# USB_OTG.net
KiCad netlist of a schematic drawn in Altium Designer
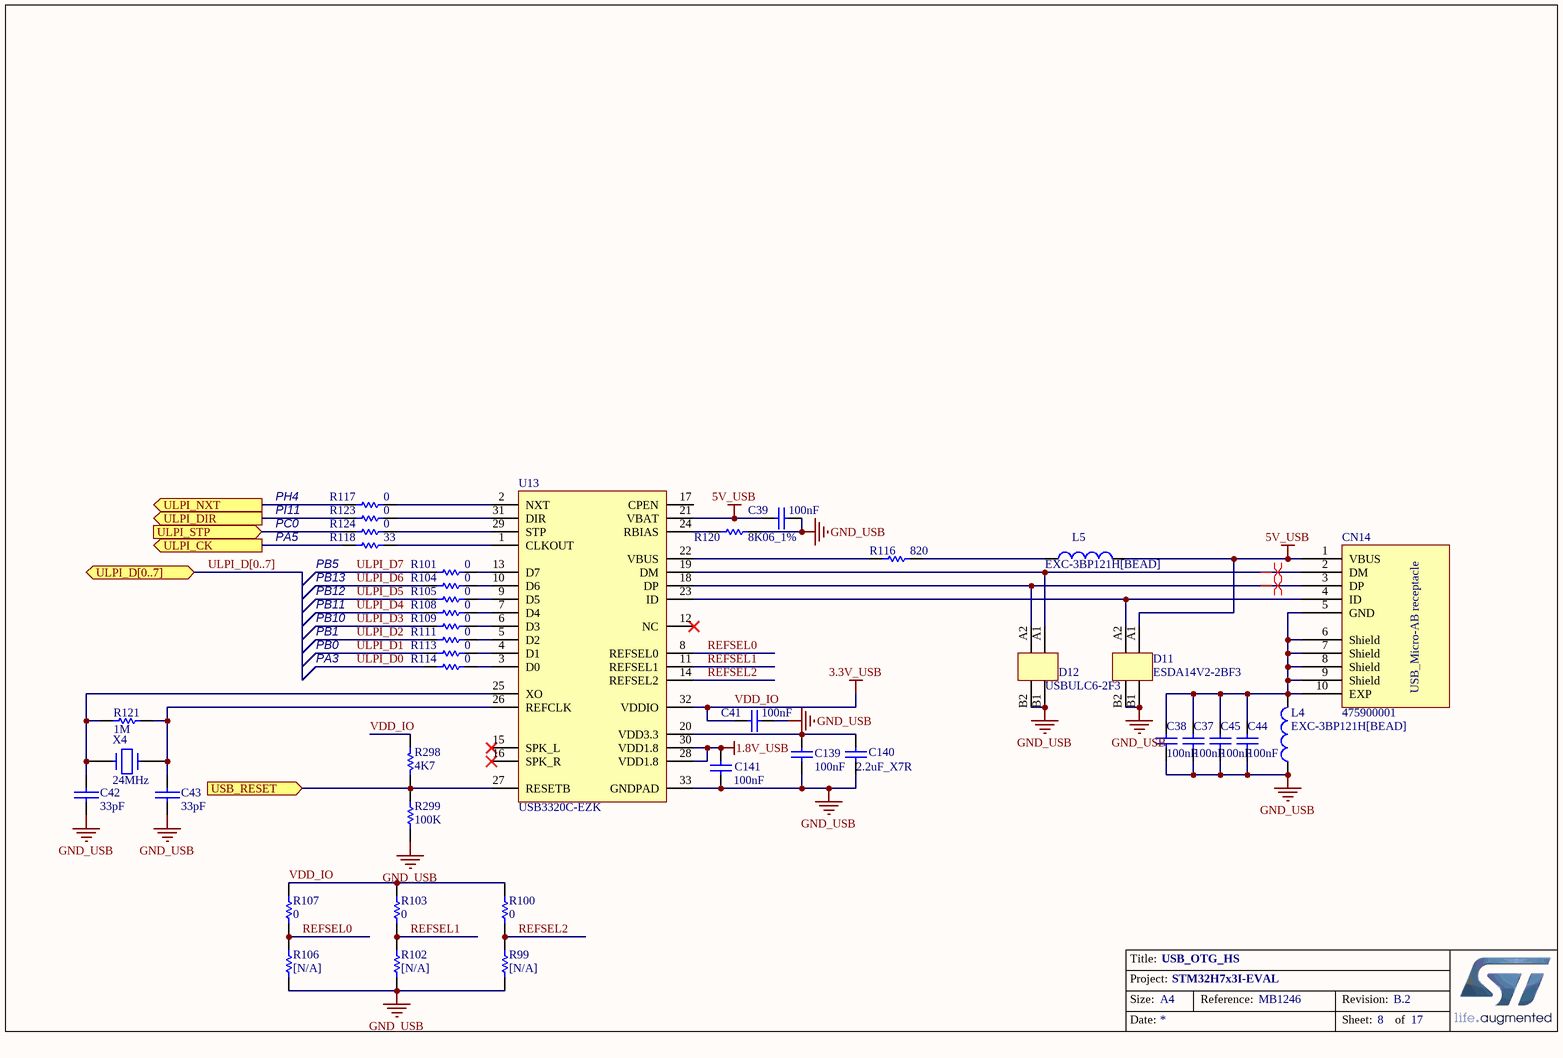
[diagram p0: USB_OTG.SchDoc]

(export (version "E")
  (design (tool "Eeschema 10.0.6"))
  (components
    (comp (ref "C37")
      (value "100nF")
      (footprint "0603C")
      (description "Capacitor")
      (fields (field (name "PUBLISHER") "Altium Limited"))
      (libsource (lib "Miscellaneous Devices") (part "Cap"))
    )
    (comp (ref "C38")
      (value "100nF")
      (footprint "0603C")
      (description "Capacitor")
      (fields (field (name "PUBLISHER") "Altium Limited"))
      (libsource (lib "Miscellaneous Devices") (part "Cap"))
    )
    (comp (ref "C39")
      (value "100nF")
      (footprint "0603C")
      (description "Capacitor")
      (fields (field (name "PUBLISHER") "Altium Limited"))
      (libsource (lib "Miscellaneous Devices") (part "Cap"))
    )
    (comp (ref "C41")
      (value "100nF")
      (footprint "0603C")
      (description "Capacitor")
      (fields (field (name "PUBLISHER") "Altium Limited"))
      (libsource (lib "Miscellaneous Devices") (part "Cap"))
    )
    (comp (ref "C42")
      (value "33pF")
      (footprint "0603C")
      (description "Capacitor")
      (libsource (lib "*") (part "CAP"))
    )
    (comp (ref "C43")
      (value "33pF")
      (footprint "0603C")
      (description "Capacitor")
      (libsource (lib "*") (part "CAP"))
    )
    (comp (ref "C44")
      (value "100nF")
      (footprint "0603C")
      (description "Capacitor")
      (fields (field (name "PUBLISHER") "Altium Limited"))
      (libsource (lib "Miscellaneous Devices") (part "Cap"))
    )
    (comp (ref "C45")
      (value "100nF")
      (footprint "0603C")
      (description "Capacitor")
      (fields (field (name "PUBLISHER") "Altium Limited"))
      (libsource (lib "Miscellaneous Devices") (part "Cap"))
    )
    (comp (ref "C139")
      (value "100nF")
      (footprint "0603C")
      (description "Capacitor")
      (fields (field (name "PUBLISHER") "Altium Limited"))
      (libsource (lib "Miscellaneous Devices") (part "Cap"))
    )
    (comp (ref "C140")
      (value "2.2uF_X7R")
      (footprint "0603C")
      (description "Capacitor")
      (fields (field (name "PUBLISHER") "Altium Limited"))
      (libsource (lib "Miscellaneous Devices") (part "Cap"))
    )
    (comp (ref "C141")
      (value "100nF")
      (footprint "0603C")
      (description "Capacitor")
      (fields (field (name "PUBLISHER") "Altium Limited"))
      (libsource (lib "Miscellaneous Devices") (part "Cap"))
    )
    (comp (ref "CN14")
      (value "475900001")
      (footprint "MOLEX_47590001")
      (libsource (lib "mb1045") (part "475900001"))
    )
    (comp (ref "D11")
      (value "ESDA14V2-2BF3")
      (footprint "BGA4_0R4_0R8X0R8")
      (libsource (lib "MB786") (part "ESDA14V2-2BF3"))
    )
    (comp (ref "D12")
      (value "USBULC6-2F3")
      (footprint "BGA4_0R4_1X1")
      (libsource (lib "MB786") (part "USBULC6-2F3"))
    )
    (comp (ref "L4")
      (value "EXC-3BP121H[BEAD]")
      (footprint "0603L")
      (description "Inductor")
      (fields (field (name "PUBLISHER") "Altium Limited"))
      (libsource (lib "Miscellaneous Devices") (part "Inductor"))
    )
    (comp (ref "L5")
      (value "EXC-3BP121H[BEAD]")
      (footprint "0603L")
      (description "Inductor")
      (fields (field (name "PUBLISHER") "Altium Limited"))
      (libsource (lib "Miscellaneous Devices") (part "Inductor"))
    )
    (comp (ref "R99")
      (value "[N/A]")
      (footprint "0603R")
      (description "Resistor")
      (fields (field (name "PUBLISHER") "Altium Limited"))
      (libsource (lib "Miscellaneous Devices") (part "Res1"))
    )
    (comp (ref "R100")
      (value "0")
      (footprint "0603R")
      (description "Resistor")
      (fields (field (name "PUBLISHER") "Altium Limited"))
      (libsource (lib "Miscellaneous Devices") (part "Res1"))
    )
    (comp (ref "R101")
      (value "0")
      (footprint "0603R")
      (description "Resistor")
      (fields (field (name "PUBLISHER") "Altium Limited"))
      (libsource (lib "Miscellaneous Devices") (part "Res1"))
    )
    (comp (ref "R102")
      (value "[N/A]")
      (footprint "0603R")
      (description "Resistor")
      (fields (field (name "PUBLISHER") "Altium Limited"))
      (libsource (lib "Miscellaneous Devices") (part "Res1"))
    )
    (comp (ref "R103")
      (value "0")
      (footprint "0603R")
      (description "Resistor")
      (fields (field (name "PUBLISHER") "Altium Limited"))
      (libsource (lib "Miscellaneous Devices") (part "Res1"))
    )
    (comp (ref "R104")
      (value "0")
      (footprint "0603R")
      (description "Resistor")
      (fields (field (name "PUBLISHER") "Altium Limited"))
      (libsource (lib "Miscellaneous Devices") (part "Res1"))
    )
    (comp (ref "R105")
      (value "0")
      (footprint "0603R")
      (description "Resistor")
      (fields (field (name "PUBLISHER") "Altium Limited"))
      (libsource (lib "Miscellaneous Devices") (part "Res1"))
    )
    (comp (ref "R106")
      (value "[N/A]")
      (footprint "0603R")
      (description "Resistor")
      (fields (field (name "PUBLISHER") "Altium Limited"))
      (libsource (lib "Miscellaneous Devices") (part "Res1"))
    )
    (comp (ref "R107")
      (value "0")
      (footprint "0603R")
      (description "Resistor")
      (fields (field (name "PUBLISHER") "Altium Limited"))
      (libsource (lib "Miscellaneous Devices") (part "Res1"))
    )
    (comp (ref "R108")
      (value "0")
      (footprint "0603R")
      (description "Resistor")
      (fields (field (name "PUBLISHER") "Altium Limited"))
      (libsource (lib "Miscellaneous Devices") (part "Res1"))
    )
    (comp (ref "R109")
      (value "0")
      (footprint "0603R")
      (description "Resistor")
      (fields (field (name "PUBLISHER") "Altium Limited"))
      (libsource (lib "Miscellaneous Devices") (part "Res1"))
    )
    (comp (ref "R111")
      (value "0")
      (footprint "0603R")
      (description "Resistor")
      (fields (field (name "PUBLISHER") "Altium Limited"))
      (libsource (lib "Miscellaneous Devices") (part "Res1"))
    )
    (comp (ref "R113")
      (value "0")
      (footprint "0603R")
      (description "Resistor")
      (fields (field (name "PUBLISHER") "Altium Limited"))
      (libsource (lib "Miscellaneous Devices") (part "Res1"))
    )
    (comp (ref "R114")
      (value "0")
      (footprint "0603R")
      (description "Resistor")
      (fields (field (name "PUBLISHER") "Altium Limited"))
      (libsource (lib "Miscellaneous Devices") (part "Res1"))
    )
    (comp (ref "R116")
      (value "820")
      (footprint "0603R")
      (description "Resistor")
      (fields (field (name "PUBLISHER") "Altium Limited"))
      (libsource (lib "Miscellaneous Devices") (part "res1"))
    )
    (comp (ref "R117")
      (value "0")
      (footprint "0603R")
      (description "Resistor")
      (fields (field (name "PUBLISHER") "Altium Limited"))
      (libsource (lib "Miscellaneous Devices") (part "Res1"))
    )
    (comp (ref "R118")
      (value "33")
      (footprint "0603R")
      (description "Resistor")
      (fields (field (name "PUBLISHER") "Altium Limited"))
      (libsource (lib "Miscellaneous Devices") (part "Res1"))
    )
    (comp (ref "R120")
      (value "8K06_1%")
      (footprint "0603R")
      (description "Resistor,8K06,0402,1%,YAGEO")
      (libsource (lib "MCD_TOOLS") (part "Res_8K06_1%_0402"))
    )
    (comp (ref "R121")
      (value "1M")
      (footprint "0603R")
      (description "Resistor")
      (fields (field (name "PUBLISHER") "Altium Limited"))
      (libsource (lib "Miscellaneous Devices") (part "Res1"))
    )
    (comp (ref "R123")
      (value "0")
      (footprint "0603R")
      (description "Resistor")
      (fields (field (name "PUBLISHER") "Altium Limited"))
      (libsource (lib "Miscellaneous Devices") (part "Res1"))
    )
    (comp (ref "R124")
      (value "0")
      (footprint "0603R")
      (description "Resistor")
      (fields (field (name "PUBLISHER") "Altium Limited"))
      (libsource (lib "Miscellaneous Devices") (part "Res1"))
    )
    (comp (ref "R298")
      (value "4K7")
      (footprint "0603R")
      (description "Resistor")
      (fields (field (name "PUBLISHER") "Altium Limited"))
      (libsource (lib "*") (part "Res1"))
    )
    (comp (ref "R299")
      (value "100K")
      (footprint "0603R")
      (description "Resistor 0402 / 0603 / 0805")
      (libsource (lib "") (part "Res1_1"))
    )
    (comp (ref "U13")
      (value "USB3320C-EZK")
      (footprint "QFN32_0R5_5X5")
      (description "USB3320C,  Hi-Speed USB Host, Device or OTG PHY with ULPI Low Pin Interface")
      (libsource (lib "MCD_TOOLS") (part "USB3320C-EZK"))
    )
    (comp (ref "X4")
      (value "24MHz")
      (footprint "XTAL1")
      (description "Crystal")
      (libsource (lib "*") (part "CRYSTAL"))
    )
  )
  (nets
    (net (code "1") (name "/REFSEL0") (class "Default")
      (node (ref "R106") (pin "2") (pinfunction "2_2") (pintype "passive"))
      (node (ref "R107") (pin "1") (pinfunction "1_1") (pintype "passive"))
      (node (ref "U13") (pin "8") (pinfunction "REFSEL0_8") (pintype "passive"))
    )
    (net (code "2") (name "/REFSEL1") (class "Default")
      (node (ref "R102") (pin "2") (pinfunction "2_2") (pintype "passive"))
      (node (ref "R103") (pin "1") (pinfunction "1_1") (pintype "passive"))
      (node (ref "U13") (pin "11") (pinfunction "REFSEL1_11") (pintype "passive"))
    )
    (net (code "3") (name "/REFSEL2") (class "Default")
      (node (ref "R100") (pin "1") (pinfunction "1_1") (pintype "passive"))
      (node (ref "R99") (pin "2") (pinfunction "2_2") (pintype "passive"))
      (node (ref "U13") (pin "14") (pinfunction "REFSEL2_14") (pintype "passive"))
    )
    (net (code "4") (name "/ULPI_CK") (class "Default")
      (node (ref "R118") (pin "2") (pinfunction "2_2") (pintype "passive"))
    )
    (net (code "5") (name "/ULPI_D0") (class "Default")
      (node (ref "R114") (pin "2") (pinfunction "2_2") (pintype "passive"))
    )
    (net (code "6") (name "/ULPI_D1") (class "Default")
      (node (ref "R113") (pin "2") (pinfunction "2_2") (pintype "passive"))
    )
    (net (code "7") (name "/ULPI_D2") (class "Default")
      (node (ref "R111") (pin "2") (pinfunction "2_2") (pintype "passive"))
    )
    (net (code "8") (name "/ULPI_D3") (class "Default")
      (node (ref "R109") (pin "2") (pinfunction "2_2") (pintype "passive"))
    )
    (net (code "9") (name "/ULPI_D4") (class "Default")
      (node (ref "R108") (pin "2") (pinfunction "2_2") (pintype "passive"))
    )
    (net (code "10") (name "/ULPI_D5") (class "Default")
      (node (ref "R105") (pin "2") (pinfunction "2_2") (pintype "passive"))
    )
    (net (code "11") (name "/ULPI_D6") (class "Default")
      (node (ref "R104") (pin "2") (pinfunction "2_2") (pintype "passive"))
    )
    (net (code "12") (name "/ULPI_D7") (class "Default")
      (node (ref "R101") (pin "2") (pinfunction "2_2") (pintype "passive"))
    )
    (net (code "13") (name "/ULPI_DIR") (class "Default")
      (node (ref "R123") (pin "2") (pinfunction "2_2") (pintype "passive"))
    )
    (net (code "15") (name "/ULPI_NXT") (class "Default")
      (node (ref "R117") (pin "2") (pinfunction "2_2") (pintype "passive"))
    )
    (net (code "16") (name "/ULPI_STP") (class "Default")
      (node (ref "R124") (pin "2") (pinfunction "2_2") (pintype "passive"))
    )
    (net (code "17") (name "/USB_RESET") (class "Default")
      (node (ref "R298") (pin "1") (pinfunction "1_1") (pintype "passive"))
      (node (ref "R299") (pin "2") (pinfunction "2_2") (pintype "passive"))
      (node (ref "U13") (pin "27") (pinfunction "RESETB_27") (pintype "passive"))
    )
    (net (code "18") (name "1.8V_USB") (class "Default")
      (node (ref "C141") (pin "1") (pinfunction "1_1") (pintype "passive"))
      (node (ref "U13") (pin "28") (pinfunction "VDD1.8_28") (pintype "passive"))
      (node (ref "U13") (pin "30") (pinfunction "VDD1.8_30") (pintype "passive"))
    )
    (net (code "19") (name "3.3V_USB") (class "Default")
      (node (ref "C41") (pin "1") (pinfunction "1_1") (pintype "passive"))
      (node (ref "R100") (pin "2") (pinfunction "2_2") (pintype "passive"))
      (node (ref "R103") (pin "2") (pinfunction "2_2") (pintype "passive"))
      (node (ref "R107") (pin "2") (pinfunction "2_2") (pintype "passive"))
      (node (ref "R298") (pin "2") (pinfunction "2_2") (pintype "passive"))
      (node (ref "U13") (pin "32") (pinfunction "VDDIO_32") (pintype "passive"))
    )
    (net (code "20") (name "5V_USB") (class "Default")
      (node (ref "C39") (pin "1") (pinfunction "1_1") (pintype "passive"))
      (node (ref "CN14") (pin "1") (pinfunction "VBUS_1") (pintype "passive"))
      (node (ref "D11") (pin "A1") (pintype "passive"))
      (node (ref "L5") (pin "2") (pinfunction "2_2") (pintype "passive"))
      (node (ref "U13") (pin "21") (pinfunction "VBAT_21") (pintype "passive"))
    )
    (net (code "21") (name "GND_USB") (class "Default")
      (node (ref "C139") (pin "2") (pinfunction "2_2") (pintype "passive"))
      (node (ref "C140") (pin "1") (pinfunction "1_1") (pintype "passive"))
      (node (ref "C141") (pin "2") (pinfunction "2_2") (pintype "passive"))
      (node (ref "C37") (pin "2") (pinfunction "2_2") (pintype "passive"))
      (node (ref "C38") (pin "2") (pinfunction "2_2") (pintype "passive"))
      (node (ref "C39") (pin "2") (pinfunction "2_2") (pintype "passive"))
      (node (ref "C41") (pin "2") (pinfunction "2_2") (pintype "passive"))
      (node (ref "C42") (pin "2") (pinfunction "2_2") (pintype "passive"))
      (node (ref "C43") (pin "2") (pinfunction "2_2") (pintype "passive"))
      (node (ref "C44") (pin "2") (pinfunction "2_2") (pintype "passive"))
      (node (ref "C45") (pin "2") (pinfunction "2_2") (pintype "passive"))
      (node (ref "D11") (pin "B1") (pintype "passive"))
      (node (ref "D11") (pin "B2") (pintype "passive"))
      (node (ref "D12") (pin "B1") (pintype "passive"))
      (node (ref "D12") (pin "B2") (pintype "passive"))
      (node (ref "L4") (pin "1") (pinfunction "1_1") (pintype "passive"))
      (node (ref "R102") (pin "1") (pinfunction "1_1") (pintype "passive"))
      (node (ref "R106") (pin "1") (pinfunction "1_1") (pintype "passive"))
      (node (ref "R120") (pin "2") (pinfunction "2_2") (pintype "passive"))
      (node (ref "R299") (pin "1") (pinfunction "1_1") (pintype "passive"))
      (node (ref "R99") (pin "1") (pinfunction "1_1") (pintype "passive"))
      (node (ref "U13") (pin "33") (pinfunction "GNDPAD_33") (pintype "passive"))
    )
    (net (code "22") (name "Net-(CN14-DM)") (class "Default")
      (node (ref "CN14") (pin "2") (pinfunction "DM_2") (pintype "passive"))
      (node (ref "D12") (pin "A1") (pintype "passive"))
      (node (ref "U13") (pin "19") (pinfunction "DM_19") (pintype "passive"))
    )
    (net (code "23") (name "Net-(CN14-DP)") (class "Default")
      (node (ref "CN14") (pin "3") (pinfunction "DP_3") (pintype "passive"))
      (node (ref "D12") (pin "A2") (pintype "passive"))
      (node (ref "U13") (pin "18") (pinfunction "DP_18") (pintype "passive"))
    )
    (net (code "24") (name "Net-(CN14-EXP)") (class "Default")
      (node (ref "C37") (pin "1") (pinfunction "1_1") (pintype "passive"))
      (node (ref "C38") (pin "1") (pinfunction "1_1") (pintype "passive"))
      (node (ref "C44") (pin "1") (pinfunction "1_1") (pintype "passive"))
      (node (ref "C45") (pin "1") (pinfunction "1_1") (pintype "passive"))
      (node (ref "CN14") (pin "10") (pinfunction "EXP_10") (pintype "passive"))
      (node (ref "CN14") (pin "5") (pinfunction "GND_5") (pintype "passive"))
      (node (ref "CN14") (pin "6") (pinfunction "Shield_6") (pintype "passive"))
      (node (ref "CN14") (pin "7") (pinfunction "Shield_7") (pintype "passive"))
      (node (ref "CN14") (pin "8") (pinfunction "Shield_8") (pintype "passive"))
      (node (ref "CN14") (pin "9") (pinfunction "Shield_9") (pintype "passive"))
      (node (ref "L4") (pin "2") (pinfunction "2_2") (pintype "passive"))
    )
    (net (code "25") (name "Net-(CN14-ID)") (class "Default")
      (node (ref "CN14") (pin "4") (pinfunction "ID_4") (pintype "passive"))
      (node (ref "D11") (pin "A2") (pintype "passive"))
      (node (ref "U13") (pin "23") (pinfunction "ID_23") (pintype "passive"))
    )
    (net (code "26") (name "Net-(L5-Pad1)") (class "Default")
      (node (ref "L5") (pin "1") (pinfunction "1_1") (pintype "passive"))
      (node (ref "R116") (pin "2") (pinfunction "2_2") (pintype "passive"))
    )
    (net (code "27") (name "Net-(U13-CLKOUT)") (class "Default")
      (node (ref "R118") (pin "1") (pinfunction "1_1") (pintype "passive"))
      (node (ref "U13") (pin "1") (pinfunction "CLKOUT_1") (pintype "passive"))
    )
    (net (code "28") (name "Net-(U13-D0)") (class "Default")
      (node (ref "R114") (pin "1") (pinfunction "1_1") (pintype "passive"))
      (node (ref "U13") (pin "3") (pinfunction "D0_3") (pintype "passive"))
    )
    (net (code "29") (name "Net-(U13-D1)") (class "Default")
      (node (ref "R113") (pin "1") (pinfunction "1_1") (pintype "passive"))
      (node (ref "U13") (pin "4") (pinfunction "D1_4") (pintype "passive"))
    )
    (net (code "30") (name "Net-(U13-D2)") (class "Default")
      (node (ref "R111") (pin "1") (pinfunction "1_1") (pintype "passive"))
      (node (ref "U13") (pin "5") (pinfunction "D2_5") (pintype "passive"))
    )
    (net (code "31") (name "Net-(U13-D3)") (class "Default")
      (node (ref "R109") (pin "1") (pinfunction "1_1") (pintype "passive"))
      (node (ref "U13") (pin "6") (pinfunction "D3_6") (pintype "passive"))
    )
    (net (code "32") (name "Net-(U13-D4)") (class "Default")
      (node (ref "R108") (pin "1") (pinfunction "1_1") (pintype "passive"))
      (node (ref "U13") (pin "7") (pinfunction "D4_7") (pintype "passive"))
    )
    (net (code "33") (name "Net-(U13-D5)") (class "Default")
      (node (ref "R105") (pin "1") (pinfunction "1_1") (pintype "passive"))
      (node (ref "U13") (pin "9") (pinfunction "D5_9") (pintype "passive"))
    )
    (net (code "34") (name "Net-(U13-D6)") (class "Default")
      (node (ref "R104") (pin "1") (pinfunction "1_1") (pintype "passive"))
      (node (ref "U13") (pin "10") (pinfunction "D6_10") (pintype "passive"))
    )
    (net (code "35") (name "Net-(U13-D7)") (class "Default")
      (node (ref "R101") (pin "1") (pinfunction "1_1") (pintype "passive"))
      (node (ref "U13") (pin "13") (pinfunction "D7_13") (pintype "passive"))
    )
    (net (code "36") (name "Net-(U13-DIR)") (class "Default")
      (node (ref "R123") (pin "1") (pinfunction "1_1") (pintype "passive"))
      (node (ref "U13") (pin "31") (pinfunction "DIR_31") (pintype "passive"))
    )
    (net (code "37") (name "Net-(U13-NXT)") (class "Default")
      (node (ref "R117") (pin "1") (pinfunction "1_1") (pintype "passive"))
      (node (ref "U13") (pin "2") (pinfunction "NXT_2") (pintype "passive"))
    )
    (net (code "38") (name "Net-(U13-RBIAS)") (class "Default")
      (node (ref "R120") (pin "1") (pinfunction "1_1") (pintype "passive"))
      (node (ref "U13") (pin "24") (pinfunction "RBIAS_24") (pintype "passive"))
    )
    (net (code "39") (name "Net-(U13-REFCLK)") (class "Default")
      (node (ref "C43") (pin "1") (pinfunction "1_1") (pintype "passive"))
      (node (ref "R121") (pin "2") (pinfunction "2_2") (pintype "passive"))
      (node (ref "U13") (pin "26") (pinfunction "REFCLK_26") (pintype "passive"))
      (node (ref "X4") (pin "1") (pinfunction "1_1") (pintype "passive"))
    )
    (net (code "40") (name "Net-(U13-STP)") (class "Default")
      (node (ref "R124") (pin "1") (pinfunction "1_1") (pintype "passive"))
      (node (ref "U13") (pin "29") (pinfunction "STP_29") (pintype "passive"))
    )
    (net (code "41") (name "Net-(U13-VBUS)") (class "Default")
      (node (ref "R116") (pin "1") (pinfunction "1_1") (pintype "passive"))
      (node (ref "U13") (pin "22") (pinfunction "VBUS_22") (pintype "passive"))
    )
    (net (code "42") (name "Net-(U13-VDD3.3)") (class "Default")
      (node (ref "C139") (pin "1") (pinfunction "1_1") (pintype "passive"))
      (node (ref "C140") (pin "2") (pinfunction "2_2") (pintype "passive"))
      (node (ref "U13") (pin "20") (pinfunction "VDD3.3_20") (pintype "passive"))
    )
    (net (code "43") (name "Net-(U13-XO)") (class "Default")
      (node (ref "C42") (pin "1") (pinfunction "1_1") (pintype "passive"))
      (node (ref "R121") (pin "1") (pinfunction "1_1") (pintype "passive"))
      (node (ref "U13") (pin "25") (pinfunction "XO_25") (pintype "passive"))
      (node (ref "X4") (pin "2") (pinfunction "2_2") (pintype "passive"))
    )
    (net (code "44") (name "unconnected-(U13-CPEN-Pad17)") (class "Default")
      (node (ref "U13") (pin "17") (pinfunction "CPEN_17") (pintype "passive"))
    )
    (net (code "45") (name "unconnected-(U13-NC-Pad12)") (class "Default")
      (node (ref "U13") (pin "12") (pinfunction "NC_12") (pintype "passive+no_connect"))
    )
    (net (code "46") (name "unconnected-(U13-SPK_L-Pad15)") (class "Default")
      (node (ref "U13") (pin "15") (pinfunction "SPK_L_15") (pintype "passive+no_connect"))
    )
    (net (code "47") (name "unconnected-(U13-SPK_R-Pad16)") (class "Default")
      (node (ref "U13") (pin "16") (pinfunction "SPK_R_16") (pintype "passive+no_connect"))
    )
  )
)
